# v1_5_USB_UART.net
KiCad netlist of a schematic drawn in EAGLE
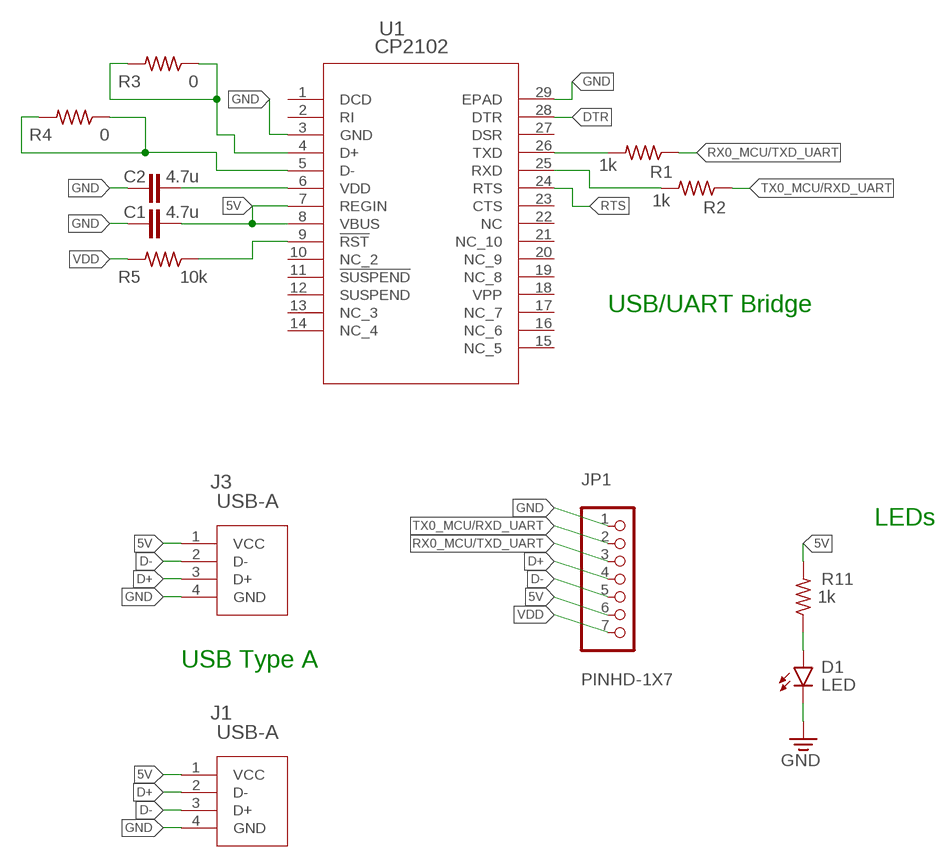
[diagram p0: schematic, sheet 1]

(export (version "E")
  (design (tool "Eeschema 10.0.6"))
  (components
    (comp (ref "C1")
      (value "4.7u")
      (footprint "eagle-import:CAPC2012X110")
      (libsource (lib "eagle-import") (part "CCHIP-0805(2012-METRIC)_"))
    )
    (comp (ref "C2")
      (value "4.7u")
      (footprint "eagle-import:CAPC2012X110")
      (libsource (lib "eagle-import") (part "CCHIP-0805(2012-METRIC)_"))
    )
    (comp (ref "D1")
      (value "LED")
      (footprint "eagle-import:LEDC2012X110N_FLAT-B")
      (libsource (lib "eagle-import") (part "CHIP-FLAT-B_0805"))
    )
    (comp (ref "J1")
      (value "USB-A")
      (footprint "eagle-import:USB-A")
      (fields
        (field (name "MANUFACTURER_PART_NUMBER") "USB-A1VSB6")
        (field (name "COPYRIGHT") "Copyright (C) 2025 Ultra Librarian. All rights reserved.")
      )
      (libsource (lib "eagle-import") (part "USB-A1VSB6_OST"))
    )
    (comp (ref "J3")
      (value "USB-A")
      (footprint "eagle-import:USB-A")
      (fields
        (field (name "MANUFACTURER_PART_NUMBER") "USB-A1VSB6")
        (field (name "COPYRIGHT") "Copyright (C) 2025 Ultra Librarian. All rights reserved.")
      )
      (libsource (lib "eagle-import") (part "USB-A1VSB6_OST"))
    )
    (comp (ref "JP1")
      (value "PINHD-1X7")
      (footprint "eagle-import:1X07")
      (libsource (lib "eagle-import") (part "PINHD-1X7"))
    )
    (comp (ref "R1")
      (value "1k")
      (footprint "eagle-import:RESC2012X65")
      (libsource (lib "eagle-import") (part "R-USCHIP-0805(2012-METRIC)_"))
    )
    (comp (ref "R2")
      (value "1k")
      (footprint "eagle-import:RESC2012X65")
      (libsource (lib "eagle-import") (part "R-USCHIP-0805(2012-METRIC)_"))
    )
    (comp (ref "R3")
      (value "0")
      (footprint "eagle-import:RESC2012X65")
      (libsource (lib "eagle-import") (part "R-USCHIP-0805(2012-METRIC)_"))
    )
    (comp (ref "R4")
      (value "0")
      (footprint "eagle-import:RESC2012X65")
      (libsource (lib "eagle-import") (part "R-USCHIP-0805(2012-METRIC)_"))
    )
    (comp (ref "R5")
      (value "10k")
      (footprint "eagle-import:RESC2012X65")
      (libsource (lib "eagle-import") (part "R-USCHIP-0805(2012-METRIC)_"))
    )
    (comp (ref "R11")
      (value "1k")
      (footprint "eagle-import:RESC2012X65")
      (libsource (lib "eagle-import") (part "R-USCHIP-0805(2012-METRIC)_"))
    )
    (comp (ref "U1")
      (value "CP2102")
      (footprint "eagle-import:QFN28_5X5_SIL")
      (fields
        (field (name "MANUFACTURER_PART_NUMBER") "CP2102-GM")
        (field (name "COPYRIGHT") "Copyright (C) 2025 Ultra Librarian. All rights reserved.")
      )
      (libsource (lib "eagle-import") (part "CP2102-GMQFN28_5X5_SIL"))
    )
  )
  (nets
    (net (code "1") (name "5V") (class "Default")
      (node (ref "C1") (pin "2") (pinfunction "2_2") (pintype "passive"))
      (node (ref "J1") (pin "1") (pinfunction "VCC_1") (pintype "passive"))
      (node (ref "J3") (pin "1") (pinfunction "VCC_1") (pintype "passive"))
      (node (ref "JP1") (pin "6") (pinfunction "6_6") (pintype "passive"))
      (node (ref "R11") (pin "2") (pinfunction "2_2") (pintype "passive"))
      (node (ref "U1") (pin "7") (pinfunction "REGIN_7") (pintype "input"))
      (node (ref "U1") (pin "8") (pinfunction "VBUS_8") (pintype "input"))
    )
    (net (code "2") (name "D+") (class "Default")
      (node (ref "J1") (pin "2") (pinfunction "D-_2") (pintype "passive"))
      (node (ref "J3") (pin "3") (pinfunction "D+_3") (pintype "passive"))
      (node (ref "JP1") (pin "4") (pinfunction "4_4") (pintype "passive"))
      (node (ref "R3") (pin "1") (pinfunction "1_1") (pintype "passive"))
      (node (ref "R3") (pin "2") (pinfunction "2_2") (pintype "passive"))
      (node (ref "U1") (pin "4") (pinfunction "D+_4") (pintype "bidirectional"))
    )
    (net (code "3") (name "D-") (class "Default")
      (node (ref "J1") (pin "3") (pinfunction "D+_3") (pintype "passive"))
      (node (ref "J3") (pin "2") (pinfunction "D-_2") (pintype "passive"))
      (node (ref "JP1") (pin "5") (pinfunction "5_5") (pintype "passive"))
      (node (ref "R4") (pin "1") (pinfunction "1_1") (pintype "passive"))
      (node (ref "R4") (pin "2") (pinfunction "2_2") (pintype "passive"))
      (node (ref "U1") (pin "5") (pinfunction "D-_5") (pintype "bidirectional"))
    )
    (net (code "4") (name "DTR") (class "Default")
      (node (ref "U1") (pin "28") (pinfunction "DTR_28") (pintype "output"))
    )
    (net (code "5") (name "GND") (class "Default")
      (node (ref "C1") (pin "1") (pinfunction "1_1") (pintype "passive"))
      (node (ref "C2") (pin "1") (pinfunction "1_1") (pintype "passive"))
      (node (ref "D1") (pin "C") (pinfunction "C_C") (pintype "passive"))
      (node (ref "J1") (pin "4") (pinfunction "GND_4") (pintype "passive"))
      (node (ref "J3") (pin "4") (pinfunction "GND_4") (pintype "passive"))
      (node (ref "JP1") (pin "1") (pinfunction "1_1") (pintype "passive"))
      (node (ref "U1") (pin "29") (pinfunction "EPAD_29") (pintype "passive"))
      (node (ref "U1") (pin "3") (pinfunction "GND_3") (pintype "power_in"))
    )
    (net (code "6") (name "Net-(D1-PadA)") (class "Default")
      (node (ref "D1") (pin "A") (pinfunction "A_A") (pintype "passive"))
      (node (ref "R11") (pin "1") (pinfunction "1_1") (pintype "passive"))
    )
    (net (code "7") (name "Net-(U1-RXD)") (class "Default")
      (node (ref "R2") (pin "2") (pinfunction "2_2") (pintype "passive"))
      (node (ref "U1") (pin "25") (pinfunction "RXD_25") (pintype "input"))
    )
    (net (code "8") (name "Net-(U1-TXD)") (class "Default")
      (node (ref "R1") (pin "2") (pinfunction "2_2") (pintype "passive"))
      (node (ref "U1") (pin "26") (pinfunction "TXD_26") (pintype "output"))
    )
    (net (code "9") (name "Net-(U1-~{RST})") (class "Default")
      (node (ref "R5") (pin "1") (pinfunction "1_1") (pintype "passive"))
      (node (ref "U1") (pin "9") (pinfunction "~{RST}_9") (pintype "bidirectional"))
    )
    (net (code "10") (name "RTS") (class "Default")
      (node (ref "U1") (pin "24") (pinfunction "RTS_24") (pintype "output"))
    )
    (net (code "11") (name "RX0_MCU{slash}TXD_UART") (class "Default")
      (node (ref "JP1") (pin "3") (pinfunction "3_3") (pintype "passive"))
      (node (ref "R1") (pin "1") (pinfunction "1_1") (pintype "passive"))
    )
    (net (code "12") (name "TX0_MCU{slash}RXD_UART") (class "Default")
      (node (ref "JP1") (pin "2") (pinfunction "2_2") (pintype "passive"))
      (node (ref "R2") (pin "1") (pinfunction "1_1") (pintype "passive"))
    )
    (net (code "13") (name "VDD") (class "Default")
      (node (ref "C2") (pin "2") (pinfunction "2_2") (pintype "passive"))
      (node (ref "JP1") (pin "7") (pinfunction "7_7") (pintype "passive"))
      (node (ref "R5") (pin "2") (pinfunction "2_2") (pintype "passive"))
      (node (ref "U1") (pin "6") (pinfunction "VDD_6") (pintype "power_in"))
    )
    (net (code "14") (name "unconnected-(U1-CTS-Pad23)") (class "Default")
      (node (ref "U1") (pin "23") (pinfunction "CTS_23") (pintype "no_connect"))
    )
    (net (code "15") (name "unconnected-(U1-DCD-Pad1)") (class "Default")
      (node (ref "U1") (pin "1") (pinfunction "DCD_1") (pintype "no_connect"))
    )
    (net (code "16") (name "unconnected-(U1-DSR-Pad27)") (class "Default")
      (node (ref "U1") (pin "27") (pinfunction "DSR_27") (pintype "no_connect"))
    )
    (net (code "17") (name "unconnected-(U1-NC-Pad22)") (class "Default")
      (node (ref "U1") (pin "22") (pinfunction "NC_22") (pintype "no_connect"))
    )
    (net (code "18") (name "unconnected-(U1-NC_2-Pad10)") (class "Default")
      (node (ref "U1") (pin "10") (pinfunction "NC_2_10") (pintype "no_connect"))
    )
    (net (code "19") (name "unconnected-(U1-NC_3-Pad13)") (class "Default")
      (node (ref "U1") (pin "13") (pinfunction "NC_3_13") (pintype "no_connect"))
    )
    (net (code "20") (name "unconnected-(U1-NC_4-Pad14)") (class "Default")
      (node (ref "U1") (pin "14") (pinfunction "NC_4_14") (pintype "no_connect"))
    )
    (net (code "21") (name "unconnected-(U1-NC_5-Pad15)") (class "Default")
      (node (ref "U1") (pin "15") (pinfunction "NC_5_15") (pintype "no_connect"))
    )
    (net (code "22") (name "unconnected-(U1-NC_6-Pad16)") (class "Default")
      (node (ref "U1") (pin "16") (pinfunction "NC_6_16") (pintype "no_connect"))
    )
    (net (code "23") (name "unconnected-(U1-NC_7-Pad17)") (class "Default")
      (node (ref "U1") (pin "17") (pinfunction "NC_7_17") (pintype "no_connect"))
    )
    (net (code "24") (name "unconnected-(U1-NC_8-Pad19)") (class "Default")
      (node (ref "U1") (pin "19") (pinfunction "NC_8_19") (pintype "no_connect"))
    )
    (net (code "25") (name "unconnected-(U1-NC_9-Pad20)") (class "Default")
      (node (ref "U1") (pin "20") (pinfunction "NC_9_20") (pintype "no_connect"))
    )
    (net (code "26") (name "unconnected-(U1-NC_10-Pad21)") (class "Default")
      (node (ref "U1") (pin "21") (pinfunction "NC_10_21") (pintype "no_connect"))
    )
    (net (code "27") (name "unconnected-(U1-RI-Pad2)") (class "Default")
      (node (ref "U1") (pin "2") (pinfunction "RI_2") (pintype "no_connect"))
    )
    (net (code "28") (name "unconnected-(U1-SUSPEND-Pad12)") (class "Default")
      (node (ref "U1") (pin "12") (pinfunction "SUSPEND_12") (pintype "no_connect"))
    )
    (net (code "29") (name "unconnected-(U1-VPP-Pad18)") (class "Default")
      (node (ref "U1") (pin "18") (pinfunction "VPP_18") (pintype "no_connect"))
    )
    (net (code "30") (name "unconnected-(U1-~{SUSPEND}-Pad11)") (class "Default")
      (node (ref "U1") (pin "11") (pinfunction "~{SUSPEND}_11") (pintype "no_connect"))
    )
  )
)
